# 14_FAN_RTC.net
KiCad netlist of a schematic drawn in Altium Designer
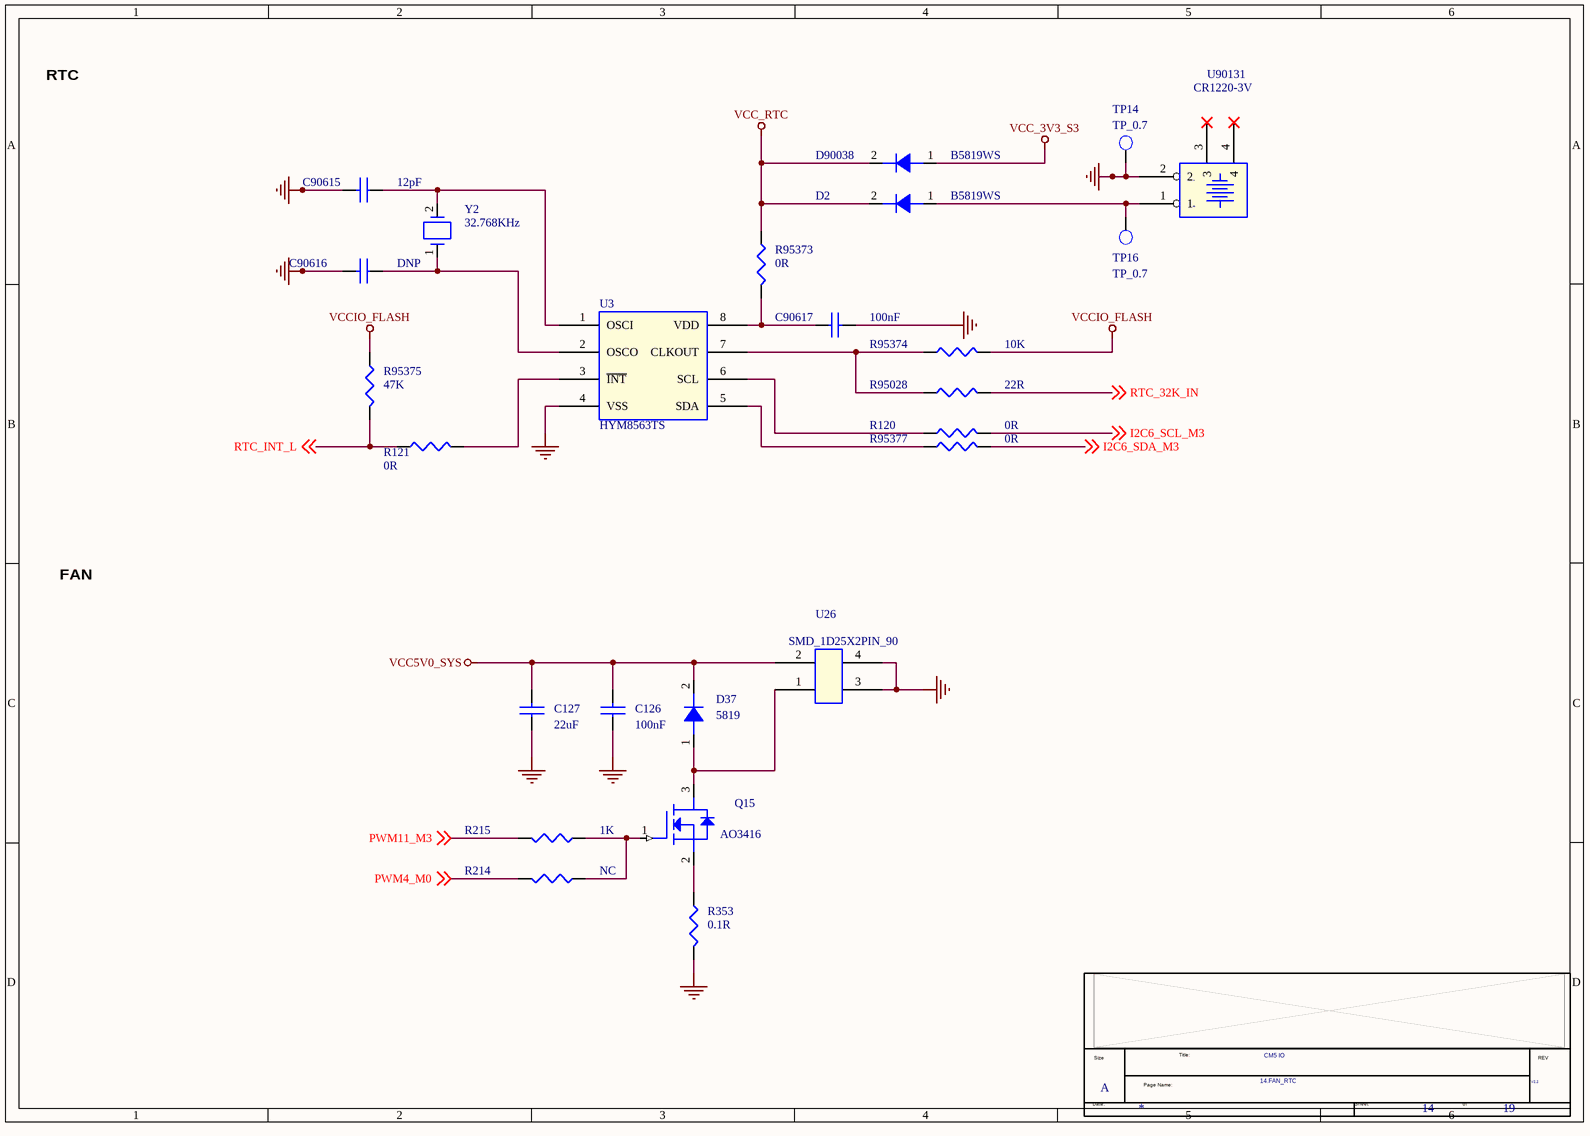
[diagram p0: 14_FAN_RTC.SchDoc]

(export (version "E")
  (design (tool "Eeschema 10.0.6"))
  (components
    (comp (ref "*")
      (value "radxa_1010")
      (fields
        (field (name "DOC") "14.FAN_RTC")
        (field (name "REVCODE") "V2.2")
        (field (name "TITLE") "CM5 IO")
        (field (name "PAGE SIZE") "A")
        (field (name "PAGE NUMBER") "14")
        (field (name "PAGE COUNT") "19")
      )
      (libsource (lib "*") (part "radxa_1010"))
    )
    (comp (ref "C126")
      (value "100nF")
      (footprint "C0402")
      (description "cap,100.00nF,+/-10%,16V,X5R,C0402")
      (fields
        (field (name "VOLTAGE") "25V")
        (field (name "MANUFACTURER") "TDK")
        (field (name "CREATED BY") "JJJ")
      )
      (libsource (lib "*") (part "CAP NP_0"))
    )
    (comp (ref "C127")
      (value "22uF")
      (footprint "C0603")
      (description "cap,22.00uF,+/-10%,10V,X5R,C0805")
      (fields
        (field (name "VOLTAGE") "25V")
        (field (name "TOLERANCE") "10%")
        (field (name "CREATED BY") "JJJ")
      )
      (libsource (lib "*") (part "CAP NP_0"))
    )
    (comp (ref "C90615")
      (value "12pF")
      (footprint "C0402")
      (description "cap,12.00pF,+/-5%,50V,C0G,C0402")
      (fields
        (field (name "VOLTAGE") "50V")
        (field (name "TOLERANCE") "5%")
        (field (name "CREATED BY") "JJJ")
      )
      (libsource (lib "*") (part "CAP NP_0"))
    )
    (comp (ref "C90616")
      (value "DNP")
      (footprint "C0402")
      (description "Did Not Place.")
      (fields (field (name "CREATED BY") "JJJ"))
      (libsource (lib "*") (part "CAP NP_0"))
    )
    (comp (ref "C90617")
      (value "100nF")
      (footprint "C0402")
      (description "cap,100.00nF,+/-10%,16V,X5R,C0402")
      (fields
        (field (name "VOLTAGE") "16V")
        (field (name "MANUFACTURER") "TDK")
        (field (name "CREATED BY") "JJJ")
      )
      (libsource (lib "*") (part "CAP NP_0"))
    )
    (comp (ref "D2")
      (value "B5819WS")
      (footprint "SOD_323")
      (description "Schottky Barrier，B5819WS SOD-323")
      (fields (field (name "MANUFACTURER") "长电") (field (name "CREATED BY") "JJJ"))
      (libsource (lib "*") (part "DIODE_Dup1"))
    )
    (comp (ref "D37")
      (value "5819")
      (footprint "SOD_123")
      (description "Schottky Barrier，B5819WS SOD-323")
      (fields (field (name "MANUFACTURER") "长电") (field (name "CREATED BY") "JJJ"))
      (libsource (lib "*") (part "DIODE_Dup1"))
    )
    (comp (ref "D90038")
      (value "B5819WS")
      (footprint "SOD_323")
      (description "Schottky Barrier，B5819WS SOD-323")
      (fields (field (name "MANUFACTURER") "长电") (field (name "CREATED BY") "JJJ"))
      (libsource (lib "*") (part "DIODE_Dup1"))
    )
    (comp (ref "Q15")
      (value "AO3416")
      (footprint "SOT23")
      (description "MOSFET-N,WNM3003 ,30V,+/-20V,4.0A,33m Ohm@Vgs=10V,43m Ohm@Vgs=4.5V,SOT23")
      (libsource (lib "*") (part "MOSFET N"))
    )
    (comp (ref "R120")
      (value "0R")
      (footprint "R0402")
      (description "通用厚膜电阻,0R,+/-5%,R0402,1/16W.")
      (fields
        (field (name "TOLERANCE") "5%")
        (field (name "MANUFACTURER") "YAGEO")
        (field (name "CREATED BY") "YTL")
      )
      (libsource (lib "*") (part "RESISTOR_1"))
    )
    (comp (ref "R121")
      (value "0R")
      (footprint "R0402")
      (description "通用厚膜电阻,0R,+/-5%,R0402,1/16W.")
      (fields
        (field (name "TOLERANCE") "5%")
        (field (name "MANUFACTURER") "YAGEO")
        (field (name "CREATED BY") "YTL")
      )
      (libsource (lib "*") (part "RESISTOR_1"))
    )
    (comp (ref "R214")
      (value "NC")
      (footprint "R0402")
      (description "通用厚膜电阻,47K,+/-5%,R0402,1/16W.")
      (fields
        (field (name "TOLERANCE") "5%")
        (field (name "MANUFACTURER") "YAGEO")
        (field (name "CREATED BY") "YTL")
      )
      (libsource (lib "*") (part "RESISTOR_1"))
    )
    (comp (ref "R215")
      (value "1K")
      (footprint "R0402")
      (description "通用厚膜电阻,47K,+/-5%,R0402,1/16W.")
      (fields
        (field (name "TOLERANCE") "5%")
        (field (name "MANUFACTURER") "YAGEO")
        (field (name "CREATED BY") "YTL")
      )
      (libsource (lib "*") (part "RESISTOR_1"))
    )
    (comp (ref "R353")
      (value "0.1R")
      (footprint "R0402")
      (description "通用厚膜电阻,10K,+/-5%,R0402,1/16W.")
      (fields
        (field (name "TOLERANCE") "5%")
        (field (name "MANUFACTURER") "YAGEO")
        (field (name "CREATED BY") "YTL")
      )
      (libsource (lib "*") (part "RESISTOR_0"))
    )
    (comp (ref "R95028")
      (value "22R")
      (footprint "R0402")
      (description "通用厚膜电阻,10K,+/-5%,R0402,1/16W.")
      (fields
        (field (name "TOLERANCE") "5%")
        (field (name "MANUFACTURER") "YAGEO")
        (field (name "CREATED BY") "YTL")
      )
      (libsource (lib "*") (part "RESISTOR_1"))
    )
    (comp (ref "R95373")
      (value "0R")
      (footprint "R0402")
      (description "通用厚膜电阻,0R,+/-1%,R0603,1/10W.")
      (fields
        (field (name "TOLERANCE") "1%")
        (field (name "MANUFACTURER") "YAGEO")
        (field (name "CREATED BY") "YTL")
      )
      (libsource (lib "*") (part "RESISTOR_1"))
    )
    (comp (ref "R95374")
      (value "10K")
      (footprint "R0402")
      (description "通用厚膜电阻,10K,+/-5%,R0402,1/16W.")
      (fields
        (field (name "TOLERANCE") "5%")
        (field (name "MANUFACTURER") "YAGEO")
        (field (name "CREATED BY") "YTL")
      )
      (libsource (lib "*") (part "RESISTOR_1"))
    )
    (comp (ref "R95375")
      (value "47K")
      (footprint "R0402")
      (description "通用厚膜电阻,47K,+/-5%,R0402,1/16W.")
      (fields
        (field (name "TOLERANCE") "5%")
        (field (name "MANUFACTURER") "YAGEO")
        (field (name "CREATED BY") "YTL")
      )
      (libsource (lib "*") (part "RESISTOR_1"))
    )
    (comp (ref "R95377")
      (value "0R")
      (footprint "R0402")
      (description "通用厚膜电阻,0R,+/-5%,R0402,1/16W.")
      (fields
        (field (name "TOLERANCE") "5%")
        (field (name "MANUFACTURER") "YAGEO")
        (field (name "CREATED BY") "YTL")
      )
      (libsource (lib "*") (part "RESISTOR_1"))
    )
    (comp (ref "TP14")
      (value "TP_0.7")
      (footprint "TEST")
      (description "Test Point 0.7mm")
      (fields (field (name "CREATED BY") "JJJ"))
      (libsource (lib "*") (part "TP"))
    )
    (comp (ref "TP16")
      (value "TP_0.7")
      (footprint "TEST")
      (description "Test Point 0.7mm")
      (fields (field (name "CREATED BY") "JJJ"))
      (libsource (lib "*") (part "TP"))
    )
    (comp (ref "U3")
      (value "HYM8563TS")
      (footprint "TSSOP8_3R10X3R10X1R10")
      (description "I2C Real Time Clock/Calendar")
      (fields (field (name "MANUFACTURER") "Haoyu（昊昱微电子）") (field (name "CREATED BY") "JJJ"))
      (libsource (lib "*") (part "RTC_HYM8563"))
    )
    (comp (ref "U26")
      (value "SMD_1D25X2PIN_90")
      (footprint "SMD_1D25X2PIN_90")
      (libsource (lib "*") (part "CON3_6"))
    )
    (comp (ref "U90131")
      (value "CR1220-3V")
      (footprint "BATTERY-20MM")
      (libsource (lib "*") (part "CON_BATTERY-20MM_0"))
    )
    (comp (ref "Y2")
      (value "32.768KHz")
      (footprint "3215_2pin")
      (description "无源晶振，32.768KHz,±20ppm，12.5pF")
      (fields (field (name "MANUFACTURER") "TKD(泰晶)") (field (name "CREATED BY") "YWQ"))
      (libsource (lib "*") (part "CRYSTAL_2P"))
    )
  )
  (nets
    (net (code "1") (name "GND") (class "Default")
      (node (ref "C126") (pin "1") (pinfunction "1_1") (pintype "passive"))
      (node (ref "C127") (pin "1") (pinfunction "1_1") (pintype "passive"))
      (node (ref "C90615") (pin "2") (pinfunction "2_2") (pintype "passive"))
      (node (ref "C90616") (pin "2") (pinfunction "2_2") (pintype "passive"))
      (node (ref "C90617") (pin "2") (pinfunction "2_2") (pintype "passive"))
      (node (ref "R353") (pin "2") (pinfunction "2_2") (pintype "passive"))
      (node (ref "TP14") (pin "1") (pinfunction "1_1") (pintype "passive"))
      (node (ref "U26") (pin "3") (pinfunction "3_3") (pintype "passive"))
      (node (ref "U26") (pin "4") (pinfunction "4_4") (pintype "passive"))
      (node (ref "U3") (pin "4") (pinfunction "VSS_4") (pintype "passive"))
      (node (ref "U90131") (pin "2") (pinfunction "2_2") (pintype "passive"))
    )
    (net (code "2") (name "I2C6_SCL_M3") (class "Default")
      (node (ref "R120") (pin "2") (pinfunction "2_2") (pintype "passive"))
    )
    (net (code "3") (name "I2C6_SDA_M3") (class "Default")
      (node (ref "R95377") (pin "2") (pinfunction "2_2") (pintype "passive"))
    )
    (net (code "4") (name "Net-(D2-A)") (class "Default")
      (node (ref "D2") (pin "1") (pinfunction "A_1") (pintype "passive"))
      (node (ref "TP16") (pin "1") (pinfunction "1_1") (pintype "passive"))
      (node (ref "U90131") (pin "1") (pinfunction "1_1") (pintype "passive"))
    )
    (net (code "5") (name "Net-(D37-A)") (class "Default")
      (node (ref "D37") (pin "1") (pinfunction "A_1") (pintype "passive"))
      (node (ref "Q15") (pin "3") (pinfunction "DRAIN_3") (pintype "passive"))
      (node (ref "U26") (pin "1") (pinfunction "1_1") (pintype "passive"))
    )
    (net (code "6") (name "Net-(Q15-GATE)") (class "Default")
      (node (ref "Q15") (pin "1") (pinfunction "GATE_1") (pintype "input"))
      (node (ref "R214") (pin "1") (pinfunction "1_1") (pintype "passive"))
      (node (ref "R215") (pin "1") (pinfunction "1_1") (pintype "passive"))
    )
    (net (code "7") (name "Net-(Q15-SOURCE)") (class "Default")
      (node (ref "Q15") (pin "2") (pinfunction "SOURCE_2") (pintype "passive"))
      (node (ref "R353") (pin "1") (pinfunction "1_1") (pintype "passive"))
    )
    (net (code "8") (name "Net-(U3-CLKOUT)") (class "Default")
      (node (ref "R95028") (pin "1") (pinfunction "1_1") (pintype "passive"))
      (node (ref "R95374") (pin "1") (pinfunction "1_1") (pintype "passive"))
      (node (ref "U3") (pin "7") (pinfunction "CLKOUT_7") (pintype "passive"))
    )
    (net (code "9") (name "Net-(U3-OSCI)") (class "Default")
      (node (ref "C90615") (pin "1") (pinfunction "1_1") (pintype "passive"))
      (node (ref "U3") (pin "1") (pinfunction "OSCI_1") (pintype "passive"))
      (node (ref "Y2") (pin "2") (pinfunction "2_2") (pintype "passive"))
    )
    (net (code "10") (name "Net-(U3-OSCO)") (class "Default")
      (node (ref "C90616") (pin "1") (pinfunction "1_1") (pintype "passive"))
      (node (ref "U3") (pin "2") (pinfunction "OSCO_2") (pintype "passive"))
      (node (ref "Y2") (pin "1") (pinfunction "1_1") (pintype "passive"))
    )
    (net (code "11") (name "Net-(U3-SCL)") (class "Default")
      (node (ref "R120") (pin "1") (pinfunction "1_1") (pintype "passive"))
      (node (ref "U3") (pin "6") (pinfunction "SCL_6") (pintype "passive"))
    )
    (net (code "12") (name "Net-(U3-SDA)") (class "Default")
      (node (ref "R95377") (pin "1") (pinfunction "1_1") (pintype "passive"))
      (node (ref "U3") (pin "5") (pinfunction "SDA_5") (pintype "passive"))
    )
    (net (code "13") (name "Net-(U3-VDD)") (class "Default")
      (node (ref "C90617") (pin "1") (pinfunction "1_1") (pintype "passive"))
      (node (ref "R95373") (pin "2") (pinfunction "2_2") (pintype "passive"))
      (node (ref "U3") (pin "8") (pinfunction "VDD_8") (pintype "passive"))
    )
    (net (code "14") (name "Net-(U3-~{INT})") (class "Default")
      (node (ref "R121") (pin "2") (pinfunction "2_2") (pintype "passive"))
      (node (ref "U3") (pin "3") (pinfunction "~{INT}_3") (pintype "passive"))
    )
    (net (code "15") (name "PWM4_M0") (class "Default")
      (node (ref "R214") (pin "2") (pinfunction "2_2") (pintype "passive"))
    )
    (net (code "16") (name "PWM11_M3") (class "Default")
      (node (ref "R215") (pin "2") (pinfunction "2_2") (pintype "passive"))
    )
    (net (code "17") (name "RTC_32K_IN") (class "Default")
      (node (ref "R95028") (pin "2") (pinfunction "2_2") (pintype "passive"))
    )
    (net (code "18") (name "RTC_INT_L") (class "Default")
      (node (ref "R121") (pin "1") (pinfunction "1_1") (pintype "passive"))
      (node (ref "R95375") (pin "2") (pinfunction "2_2") (pintype "passive"))
    )
    (net (code "19") (name "VCC5V0_SYS") (class "Default")
      (node (ref "C126") (pin "2") (pinfunction "2_2") (pintype "passive"))
      (node (ref "C127") (pin "2") (pinfunction "2_2") (pintype "passive"))
      (node (ref "D37") (pin "2") (pinfunction "K_2") (pintype "passive"))
      (node (ref "U26") (pin "2") (pinfunction "2_2") (pintype "passive"))
    )
    (net (code "20") (name "VCCIO_FLASH") (class "Default")
      (node (ref "R95374") (pin "2") (pinfunction "2_2") (pintype "passive"))
      (node (ref "R95375") (pin "1") (pinfunction "1_1") (pintype "passive"))
    )
    (net (code "21") (name "VCC_3V3_S3") (class "Default")
      (node (ref "D90038") (pin "1") (pinfunction "A_1") (pintype "passive"))
    )
    (net (code "22") (name "VCC_RTC") (class "Default")
      (node (ref "D2") (pin "2") (pinfunction "K_2") (pintype "passive"))
      (node (ref "D90038") (pin "2") (pinfunction "K_2") (pintype "passive"))
      (node (ref "R95373") (pin "1") (pinfunction "1_1") (pintype "passive"))
    )
    (net (code "23") (name "unconnected-(U90131-Pad3)") (class "Default")
      (node (ref "U90131") (pin "3") (pinfunction "3_3") (pintype "passive+no_connect"))
    )
    (net (code "24") (name "unconnected-(U90131-Pad4)") (class "Default")
      (node (ref "U90131") (pin "4") (pinfunction "4_4") (pintype "passive+no_connect"))
    )
  )
)
